# Output_stages.net
KiCad netlist of a schematic drawn in Altium Designer
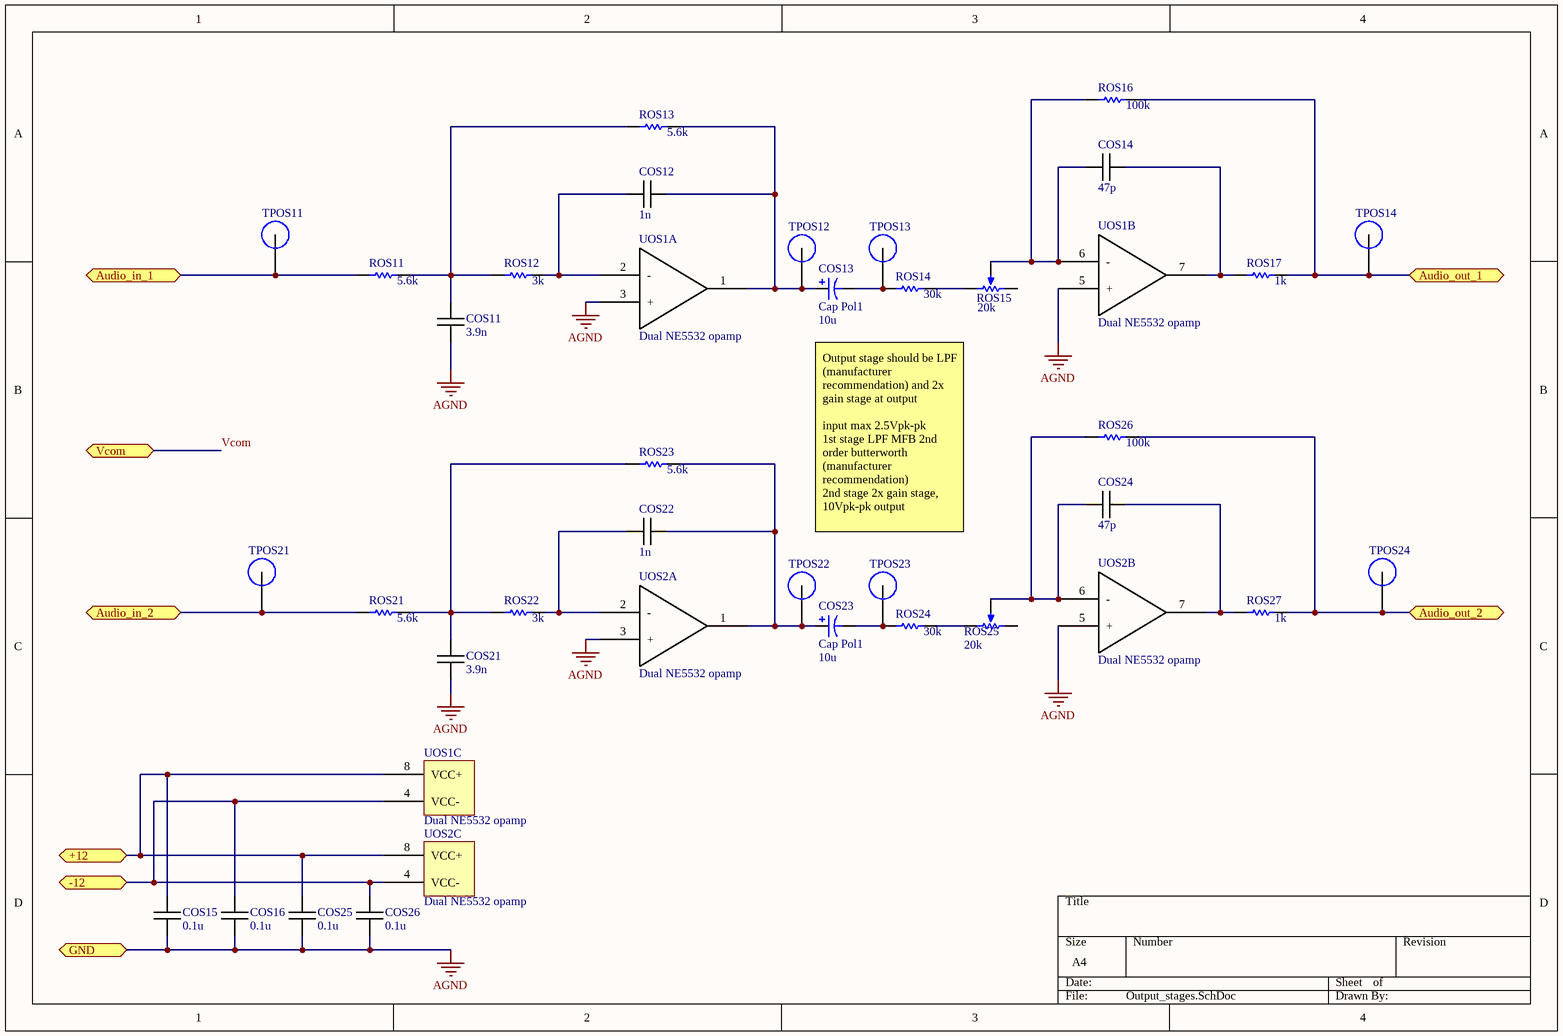
[diagram p0: Output_stages.SchDoc]

(export (version "E")
  (design (tool "Eeschema 10.0.6"))
  (components
    (comp (ref "COS11")
      (value "3.9n")
      (footprint "C 0603 / 1608")
      (libsource (lib "Standard") (part "Capacitor"))
    )
    (comp (ref "COS12")
      (value "1n")
      (footprint "C 0603 / 1608")
      (libsource (lib "Standard") (part "Capacitor"))
    )
    (comp (ref "COS13")
      (value "Cap Pol1")
      (footprint "C-RAD-4.5")
      (description "Polarized Capacitor (Radial)")
      (fields (field (name "ALTIUM_VALUE") "10u") (field (name "PUBLISHER") "Altium Limited"))
      (libsource (lib "Miscellaneous Devices") (part "Cap Pol1"))
    )
    (comp (ref "COS14")
      (value "47p")
      (footprint "C 0603 / 1608")
      (libsource (lib "Standard") (part "Capacitor"))
    )
    (comp (ref "COS15")
      (value "0.1u")
      (footprint "C 0603 / 1608")
      (libsource (lib "Standard") (part "Capacitor"))
    )
    (comp (ref "COS16")
      (value "0.1u")
      (footprint "C 0603 / 1608")
      (libsource (lib "Standard") (part "Capacitor"))
    )
    (comp (ref "COS21")
      (value "3.9n")
      (footprint "C 0603 / 1608")
      (libsource (lib "Standard") (part "Capacitor"))
    )
    (comp (ref "COS22")
      (value "1n")
      (footprint "C 0603 / 1608")
      (libsource (lib "Standard") (part "Capacitor"))
    )
    (comp (ref "COS23")
      (value "Cap Pol1")
      (footprint "C-RAD-4.5")
      (description "Polarized Capacitor (Radial)")
      (fields (field (name "ALTIUM_VALUE") "10u") (field (name "PUBLISHER") "Altium Limited"))
      (libsource (lib "Miscellaneous Devices") (part "Cap Pol1"))
    )
    (comp (ref "COS24")
      (value "47p")
      (footprint "C 0603 / 1608")
      (libsource (lib "Standard") (part "Capacitor"))
    )
    (comp (ref "COS25")
      (value "0.1u")
      (footprint "C 0603 / 1608")
      (libsource (lib "Standard") (part "Capacitor"))
    )
    (comp (ref "COS26")
      (value "0.1u")
      (footprint "C 0603 / 1608")
      (libsource (lib "Standard") (part "Capacitor"))
    )
    (comp (ref "ROS11")
      (value "5.6k")
      (footprint "RES0603R")
      (description "Resistor")
      (fields (field (name "PUBLISHER") "Altium Limited"))
      (libsource (lib "Standard") (part "Res1"))
    )
    (comp (ref "ROS12")
      (value "3k")
      (footprint "RES0603R")
      (description "Resistor")
      (fields (field (name "PUBLISHER") "Altium Limited"))
      (libsource (lib "Standard") (part "Res1"))
    )
    (comp (ref "ROS13")
      (value "5.6k")
      (footprint "RES0603R")
      (description "Resistor")
      (fields (field (name "PUBLISHER") "Altium Limited"))
      (libsource (lib "Standard") (part "Res1"))
    )
    (comp (ref "ROS14")
      (value "30k")
      (footprint "RES0603R")
      (description "Resistor")
      (fields (field (name "PUBLISHER") "Altium Limited"))
      (libsource (lib "Standard") (part "Res1"))
    )
    (comp (ref "ROS15")
      (value "20k")
      (footprint "SMD_POT_3x3mm")
      (description "Potentiometer")
      (fields (field (name "PUBLISHER") "Altium Limited"))
      (libsource (lib "Standard") (part "RPot"))
    )
    (comp (ref "ROS16")
      (value "100k")
      (footprint "RES0603R")
      (description "Resistor")
      (fields (field (name "PUBLISHER") "Altium Limited"))
      (libsource (lib "Standard") (part "Res1"))
    )
    (comp (ref "ROS17")
      (value "1k")
      (footprint "RES0603R")
      (description "Resistor")
      (fields (field (name "PUBLISHER") "Altium Limited"))
      (libsource (lib "Standard") (part "Res1"))
    )
    (comp (ref "ROS21")
      (value "5.6k")
      (footprint "RES0603R")
      (description "Resistor")
      (fields (field (name "PUBLISHER") "Altium Limited"))
      (libsource (lib "Standard") (part "Res1"))
    )
    (comp (ref "ROS22")
      (value "3k")
      (footprint "RES0603R")
      (description "Resistor")
      (fields (field (name "PUBLISHER") "Altium Limited"))
      (libsource (lib "Standard") (part "Res1"))
    )
    (comp (ref "ROS23")
      (value "5.6k")
      (footprint "RES0603R")
      (description "Resistor")
      (fields (field (name "PUBLISHER") "Altium Limited"))
      (libsource (lib "Standard") (part "Res1"))
    )
    (comp (ref "ROS24")
      (value "30k")
      (footprint "RES0603R")
      (description "Resistor")
      (fields (field (name "PUBLISHER") "Altium Limited"))
      (libsource (lib "Standard") (part "Res1"))
    )
    (comp (ref "ROS25")
      (value "20k")
      (footprint "SMD_POT_3x3mm")
      (description "Potentiometer")
      (fields (field (name "PUBLISHER") "Altium Limited"))
      (libsource (lib "Standard") (part "RPot"))
    )
    (comp (ref "ROS26")
      (value "100k")
      (footprint "RES0603R")
      (description "Resistor")
      (fields (field (name "PUBLISHER") "Altium Limited"))
      (libsource (lib "Standard") (part "Res1"))
    )
    (comp (ref "ROS27")
      (value "1k")
      (footprint "RES0603R")
      (description "Resistor")
      (fields (field (name "PUBLISHER") "Altium Limited"))
      (libsource (lib "Standard") (part "Res1"))
    )
    (comp (ref "TPOS11")
      (value "Test Point")
      (footprint "Test POint")
      (libsource (lib "Standard") (part "Test Point"))
    )
    (comp (ref "TPOS12")
      (value "Test Point")
      (footprint "Test POint")
      (libsource (lib "Standard") (part "Test Point"))
    )
    (comp (ref "TPOS13")
      (value "Test Point")
      (footprint "Test POint")
      (libsource (lib "Standard") (part "Test Point"))
    )
    (comp (ref "TPOS14")
      (value "Test Point")
      (footprint "Test POint")
      (libsource (lib "Standard") (part "Test Point"))
    )
    (comp (ref "TPOS21")
      (value "Test Point")
      (footprint "Test POint")
      (libsource (lib "Standard") (part "Test Point"))
    )
    (comp (ref "TPOS22")
      (value "Test Point")
      (footprint "Test POint")
      (libsource (lib "Standard") (part "Test Point"))
    )
    (comp (ref "TPOS23")
      (value "Test Point")
      (footprint "Test POint")
      (libsource (lib "Standard") (part "Test Point"))
    )
    (comp (ref "TPOS24")
      (value "Test Point")
      (footprint "Test POint")
      (libsource (lib "Standard") (part "Test Point"))
    )
    (comp (ref "UOS1")
      (value "Dual NE5532 opamp")
      (footprint "SOIC-8")
      (libsource (lib "") (part "NE5532_1"))
    )
    (comp (ref "UOS2")
      (value "Dual NE5532 opamp")
      (footprint "SOIC-8")
      (libsource (lib "") (part "NE5532_1"))
    )
  )
  (nets
    (net (code "1") (name "/+12") (class "Default")
      (node (ref "COS15") (pin "2") (pinfunction "1_2") (pintype "passive"))
      (node (ref "COS25") (pin "2") (pinfunction "1_2") (pintype "passive"))
      (node (ref "UOS1") (pin "8") (pinfunction "VCC+_8") (pintype "passive"))
      (node (ref "UOS2") (pin "8") (pinfunction "VCC+_8") (pintype "passive"))
    )
    (net (code "2") (name "/-12") (class "Default")
      (node (ref "COS16") (pin "2") (pinfunction "1_2") (pintype "passive"))
      (node (ref "COS26") (pin "2") (pinfunction "1_2") (pintype "passive"))
      (node (ref "UOS1") (pin "4") (pinfunction "VCC-_4") (pintype "passive"))
      (node (ref "UOS2") (pin "4") (pinfunction "VCC-_4") (pintype "passive"))
    )
    (net (code "3") (name "/Audio_in_1") (class "Default")
      (node (ref "ROS11") (pin "1") (pinfunction "1_1") (pintype "passive"))
      (node (ref "TPOS11") (pin "1") (pintype "passive"))
    )
    (net (code "4") (name "/Audio_in_2") (class "Default")
      (node (ref "ROS21") (pin "1") (pinfunction "1_1") (pintype "passive"))
      (node (ref "TPOS21") (pin "1") (pintype "passive"))
    )
    (net (code "5") (name "/Audio_out_1") (class "Default")
      (node (ref "ROS16") (pin "2") (pinfunction "2_2") (pintype "passive"))
      (node (ref "ROS17") (pin "2") (pinfunction "2_2") (pintype "passive"))
      (node (ref "TPOS14") (pin "1") (pintype "passive"))
    )
    (net (code "6") (name "/Audio_out_2") (class "Default")
      (node (ref "ROS26") (pin "2") (pinfunction "2_2") (pintype "passive"))
      (node (ref "ROS27") (pin "2") (pinfunction "2_2") (pintype "passive"))
      (node (ref "TPOS24") (pin "1") (pintype "passive"))
    )
    (net (code "8") (name "AGND") (class "Default")
      (node (ref "COS11") (pin "1") (pinfunction "1_1") (pintype "passive"))
      (node (ref "COS15") (pin "1") (pinfunction "1_1") (pintype "passive"))
      (node (ref "COS16") (pin "1") (pinfunction "1_1") (pintype "passive"))
      (node (ref "COS21") (pin "1") (pinfunction "1_1") (pintype "passive"))
      (node (ref "COS25") (pin "1") (pinfunction "1_1") (pintype "passive"))
      (node (ref "COS26") (pin "1") (pinfunction "1_1") (pintype "passive"))
      (node (ref "UOS1") (pin "3") (pinfunction "+_3") (pintype "passive"))
      (node (ref "UOS1") (pin "5") (pinfunction "+_5") (pintype "passive"))
      (node (ref "UOS2") (pin "3") (pinfunction "+_3") (pintype "passive"))
      (node (ref "UOS2") (pin "5") (pinfunction "+_5") (pintype "passive"))
    )
    (net (code "9") (name "Net-(COS11-1-Pad2)") (class "Default")
      (node (ref "COS11") (pin "2") (pinfunction "1_2") (pintype "passive"))
      (node (ref "ROS11") (pin "2") (pinfunction "2_2") (pintype "passive"))
      (node (ref "ROS12") (pin "1") (pinfunction "1_1") (pintype "passive"))
      (node (ref "ROS13") (pin "1") (pinfunction "1_1") (pintype "passive"))
    )
    (net (code "10") (name "Net-(COS13-Pad2)") (class "Default")
      (node (ref "COS13") (pin "2") (pinfunction "2_2") (pintype "passive"))
      (node (ref "ROS14") (pin "1") (pinfunction "1_1") (pintype "passive"))
      (node (ref "TPOS13") (pin "1") (pintype "passive"))
    )
    (net (code "11") (name "Net-(COS21-1-Pad2)") (class "Default")
      (node (ref "COS21") (pin "2") (pinfunction "1_2") (pintype "passive"))
      (node (ref "ROS21") (pin "2") (pinfunction "2_2") (pintype "passive"))
      (node (ref "ROS22") (pin "1") (pinfunction "1_1") (pintype "passive"))
      (node (ref "ROS23") (pin "1") (pinfunction "1_1") (pintype "passive"))
    )
    (net (code "12") (name "Net-(COS23-Pad2)") (class "Default")
      (node (ref "COS23") (pin "2") (pinfunction "2_2") (pintype "passive"))
      (node (ref "ROS24") (pin "1") (pinfunction "1_1") (pintype "passive"))
      (node (ref "TPOS23") (pin "1") (pintype "passive"))
    )
    (net (code "13") (name "Net-(ROS15-BOT)") (class "Default")
      (node (ref "ROS14") (pin "2") (pinfunction "2_2") (pintype "passive"))
      (node (ref "ROS15") (pin "2") (pinfunction "BOT_2") (pintype "passive"))
    )
    (net (code "14") (name "Net-(ROS15-TAP)") (class "Default")
      (node (ref "COS14") (pin "1") (pinfunction "1_1") (pintype "passive"))
      (node (ref "ROS15") (pin "3") (pinfunction "TAP_3") (pintype "passive"))
      (node (ref "ROS16") (pin "1") (pinfunction "1_1") (pintype "passive"))
      (node (ref "UOS1") (pin "6") (pinfunction "-_6") (pintype "passive"))
    )
    (net (code "15") (name "Net-(ROS25-BOT)") (class "Default")
      (node (ref "ROS24") (pin "2") (pinfunction "2_2") (pintype "passive"))
      (node (ref "ROS25") (pin "2") (pinfunction "BOT_2") (pintype "passive"))
    )
    (net (code "16") (name "Net-(ROS25-TAP)") (class "Default")
      (node (ref "COS24") (pin "1") (pinfunction "1_1") (pintype "passive"))
      (node (ref "ROS25") (pin "3") (pinfunction "TAP_3") (pintype "passive"))
      (node (ref "ROS26") (pin "1") (pinfunction "1_1") (pintype "passive"))
      (node (ref "UOS2") (pin "6") (pinfunction "-_6") (pintype "passive"))
    )
    (net (code "17") (name "Net-(UOS1A--)") (class "Default")
      (node (ref "COS12") (pin "1") (pinfunction "1_1") (pintype "passive"))
      (node (ref "ROS12") (pin "2") (pinfunction "2_2") (pintype "passive"))
      (node (ref "UOS1") (pin "2") (pinfunction "-_2") (pintype "passive"))
    )
    (net (code "18") (name "Net-(UOS1A-OUT)") (class "Default")
      (node (ref "COS12") (pin "2") (pinfunction "1_2") (pintype "passive"))
      (node (ref "COS13") (pin "1") (pinfunction "1_1") (pintype "passive"))
      (node (ref "ROS13") (pin "2") (pinfunction "2_2") (pintype "passive"))
      (node (ref "TPOS12") (pin "1") (pintype "passive"))
      (node (ref "UOS1") (pin "1") (pinfunction "OUT_1") (pintype "passive"))
    )
    (net (code "19") (name "Net-(UOS1B-OUT)") (class "Default")
      (node (ref "COS14") (pin "2") (pinfunction "1_2") (pintype "passive"))
      (node (ref "ROS17") (pin "1") (pinfunction "1_1") (pintype "passive"))
      (node (ref "UOS1") (pin "7") (pinfunction "OUT_7") (pintype "passive"))
    )
    (net (code "20") (name "Net-(UOS2A--)") (class "Default")
      (node (ref "COS22") (pin "1") (pinfunction "1_1") (pintype "passive"))
      (node (ref "ROS22") (pin "2") (pinfunction "2_2") (pintype "passive"))
      (node (ref "UOS2") (pin "2") (pinfunction "-_2") (pintype "passive"))
    )
    (net (code "21") (name "Net-(UOS2A-OUT)") (class "Default")
      (node (ref "COS22") (pin "2") (pinfunction "1_2") (pintype "passive"))
      (node (ref "COS23") (pin "1") (pinfunction "1_1") (pintype "passive"))
      (node (ref "ROS23") (pin "2") (pinfunction "2_2") (pintype "passive"))
      (node (ref "TPOS22") (pin "1") (pintype "passive"))
      (node (ref "UOS2") (pin "1") (pinfunction "OUT_1") (pintype "passive"))
    )
    (net (code "22") (name "Net-(UOS2B-OUT)") (class "Default")
      (node (ref "COS24") (pin "2") (pinfunction "1_2") (pintype "passive"))
      (node (ref "ROS27") (pin "1") (pinfunction "1_1") (pintype "passive"))
      (node (ref "UOS2") (pin "7") (pinfunction "OUT_7") (pintype "passive"))
    )
    (net (code "23") (name "unconnected-(ROS15-TOP-Pad1)") (class "Default")
      (node (ref "ROS15") (pin "1") (pinfunction "TOP_1") (pintype "passive"))
    )
    (net (code "24") (name "unconnected-(ROS25-TOP-Pad1)") (class "Default")
      (node (ref "ROS25") (pin "1") (pinfunction "TOP_1") (pintype "passive"))
    )
  )
)
